# pic_k42.net
KiCad netlist of a schematic drawn in EAGLE
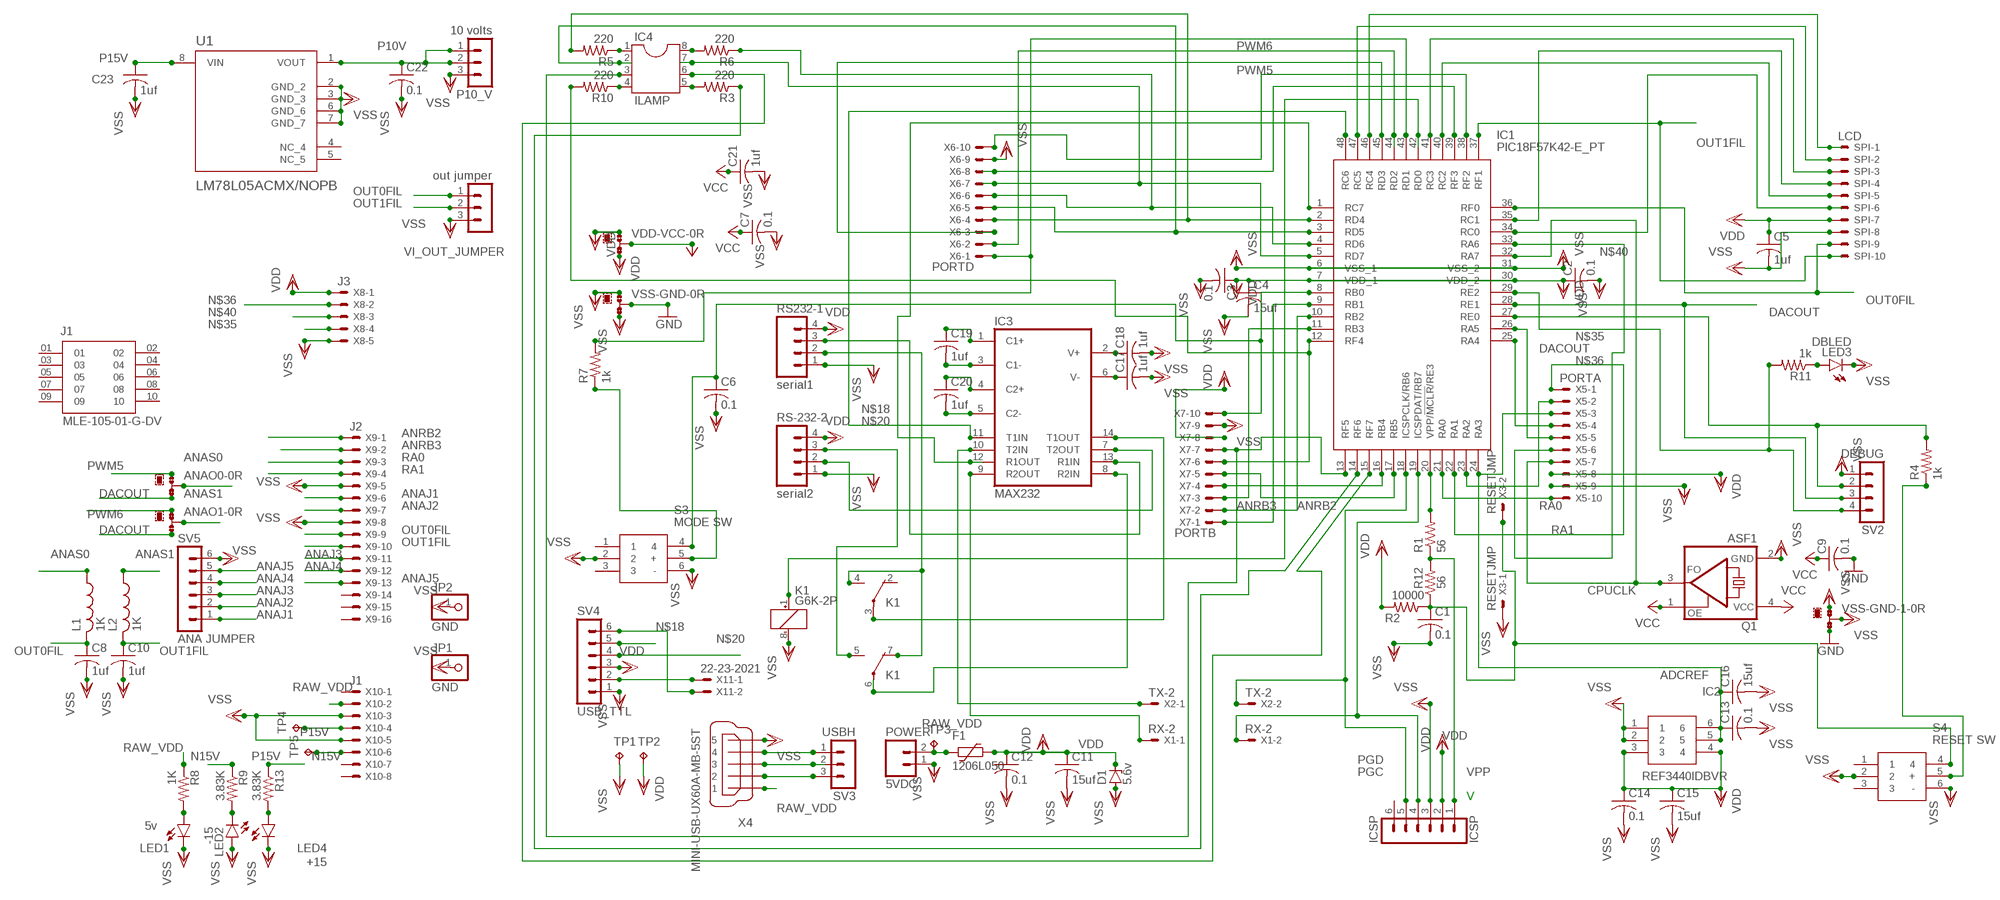
[diagram p0: schematic, sheet 1]

(export (version "E")
  (design (tool "Eeschema 10.0.6"))
  (components
    (comp (ref "ANAO0")
      (value "PS V")
      (footprint "eagle-import:A0R-JMP")
      (libsource (lib "eagle-import") (part "0R-JUMPA"))
    )
    (comp (ref "ANAO1")
      (value "PS I")
      (footprint "eagle-import:A0R-JMP")
      (libsource (lib "eagle-import") (part "0R-JUMPA"))
    )
    (comp (ref "C1")
      (value "0.1")
      (footprint "eagle-import:C1206")
      (libsource (lib "eagle-import") (part "C-USC1206"))
    )
    (comp (ref "C2")
      (value "0.1")
      (footprint "eagle-import:C1206")
      (libsource (lib "eagle-import") (part "C-USC1206"))
    )
    (comp (ref "C3")
      (value "0.1")
      (footprint "eagle-import:C1206")
      (libsource (lib "eagle-import") (part "C-USC1206"))
    )
    (comp (ref "C4")
      (value "15uf")
      (footprint "eagle-import:C1206")
      (libsource (lib "eagle-import") (part "C-USC1206"))
    )
    (comp (ref "C5")
      (value "1uf")
      (footprint "eagle-import:C0805")
      (libsource (lib "eagle-import") (part "C-USC0805"))
    )
    (comp (ref "C6")
      (value "0.1")
      (footprint "eagle-import:C1206")
      (libsource (lib "eagle-import") (part "C-USC1206"))
    )
    (comp (ref "C7")
      (value "0.1")
      (footprint "eagle-import:C1206")
      (libsource (lib "eagle-import") (part "C-USC1206"))
    )
    (comp (ref "C8")
      (value "1uf")
      (footprint "eagle-import:C0805")
      (libsource (lib "eagle-import") (part "C-USC0805"))
    )
    (comp (ref "C9")
      (value "0.1")
      (footprint "eagle-import:C1206")
      (libsource (lib "eagle-import") (part "C-USC1206"))
    )
    (comp (ref "C10")
      (value "1uf")
      (footprint "eagle-import:C0805")
      (libsource (lib "eagle-import") (part "C-USC0805"))
    )
    (comp (ref "C11")
      (value "15uf")
      (footprint "eagle-import:C1206")
      (libsource (lib "eagle-import") (part "C-USC1206"))
    )
    (comp (ref "C12")
      (value "0.1")
      (footprint "eagle-import:C1206")
      (libsource (lib "eagle-import") (part "C-USC1206"))
    )
    (comp (ref "C13")
      (value "0.1")
      (footprint "eagle-import:C1206")
      (libsource (lib "eagle-import") (part "C-USC1206"))
    )
    (comp (ref "C14")
      (value "0.1")
      (footprint "eagle-import:C1206")
      (libsource (lib "eagle-import") (part "C-USC1206"))
    )
    (comp (ref "C15")
      (value "15uf")
      (footprint "eagle-import:C1206")
      (libsource (lib "eagle-import") (part "C-USC1206"))
    )
    (comp (ref "C16")
      (value "15uf")
      (footprint "eagle-import:C1206")
      (libsource (lib "eagle-import") (part "C-USC1206"))
    )
    (comp (ref "C17")
      (value "1uf")
      (footprint "eagle-import:C0805")
      (libsource (lib "eagle-import") (part "C-USC0805"))
    )
    (comp (ref "C18")
      (value "1uf")
      (footprint "eagle-import:C0805")
      (libsource (lib "eagle-import") (part "C-USC0805"))
    )
    (comp (ref "C19")
      (value "1uf")
      (footprint "eagle-import:C0805")
      (libsource (lib "eagle-import") (part "C-USC0805"))
    )
    (comp (ref "C20")
      (value "1uf")
      (footprint "eagle-import:C0805")
      (libsource (lib "eagle-import") (part "C-USC0805"))
    )
    (comp (ref "C21")
      (value "1uf")
      (footprint "eagle-import:C0805")
      (libsource (lib "eagle-import") (part "C-USC0805"))
    )
    (comp (ref "C22")
      (value "0.1")
      (footprint "eagle-import:C1206")
      (libsource (lib "eagle-import") (part "C-USC1206"))
    )
    (comp (ref "C23")
      (value "1uf")
      (footprint "eagle-import:C0805")
      (libsource (lib "eagle-import") (part "C-USC0805"))
    )
    (comp (ref "D1")
      (value "5.6v")
      (footprint "eagle-import:DO34Z7")
      (libsource (lib "eagle-import") (part "ZENER-DIODEDO34-7"))
    )
    (comp (ref "F1")
      (value "1206L050")
      (footprint "eagle-import:1206L")
      (fields (field (name "MF") "Littelfuse"))
      (libsource (lib "eagle-import") (part "?1206L050"))
    )
    (comp (ref "IC1")
      (value "PIC18F57K42-E_PT")
      (footprint "eagle-import:QFP50P900X900X120-48N")
      (fields
        (field (name "MANUFACTURER_PART_NUMBER") "PIC18F57K42-E/PT")
        (field (name "MOUSER_PART_NUMBER") "579-PIC18F57K42-E/PT")
      )
      (libsource (lib "eagle-import") (part "PIC18F57K42-E_PT"))
    )
    (comp (ref "IC2")
      (value "REF3440IDBVR")
      (footprint "eagle-import:SOP95P280X145-6N")
      (libsource (lib "eagle-import") (part "REF3440IDBVR"))
    )
    (comp (ref "IC3")
      (value "MAX232")
      (footprint "eagle-import:DIL16")
      (fields (field (name "MF") "MAXIM") (field (name "MPN") "MAX232ACPE+"))
      (libsource (lib "eagle-import") (part "MAX232"))
    )
    (comp (ref "IC4")
      (value "ILAMP")
      (footprint "eagle-import:SOCKET-08")
      (libsource (lib "eagle-import") (part "DIL8S"))
    )
    (comp (ref "ICSP")
      (value "ICSP")
      (footprint "eagle-import:MA06-1")
      (libsource (lib "eagle-import") (part "MA06-1"))
    )
    (comp (ref "J1")
      (value "MLE-105-01-G-DV")
      (footprint "eagle-import:SAMTEC_MLE-105-01-G-DV")
      (fields (field (name "MANUFACTURER") "SAMTEC "))
      (libsource (lib "eagle-import") (part "MLE-105-01-G-DV"))
    )
    (comp (ref "JP1")
      (value "GND")
      (footprint "eagle-import:1X01")
      (libsource (lib "eagle-import") (part "PINHD-1X1"))
    )
    (comp (ref "JP2")
      (value "GND")
      (footprint "eagle-import:1X01")
      (libsource (lib "eagle-import") (part "PINHD-1X1"))
    )
    (comp (ref "K1")
      (value "G6K-2P")
      (footprint "eagle-import:G6K-2P")
      (fields (field (name "MF") "OMRON COMPONENTS USA") (field (name "MPN") "G6K-2P DC3"))
      (libsource (lib "eagle-import") (part "G6K-2P"))
    )
    (comp (ref "L1")
      (value "1K")
      (footprint "eagle-import:L2012C")
      (libsource (lib "eagle-import") (part "L-USL2012C"))
    )
    (comp (ref "L2")
      (value "1K")
      (footprint "eagle-import:L2012C")
      (libsource (lib "eagle-import") (part "L-USL2012C"))
    )
    (comp (ref "LED1")
      (value "5v")
      (footprint "eagle-import:CHIPLED_1206")
      (libsource (lib "eagle-import") (part "LEDCHIPLED_1206"))
    )
    (comp (ref "LED2")
      (value "-15")
      (footprint "eagle-import:CHIPLED_1206")
      (libsource (lib "eagle-import") (part "LEDCHIPLED_1206"))
    )
    (comp (ref "LED3")
      (value "DBLED")
      (footprint "eagle-import:CHIPLED_1206")
      (libsource (lib "eagle-import") (part "LEDCHIPLED_1206"))
    )
    (comp (ref "LED4")
      (value "+15")
      (footprint "eagle-import:CHIPLED_1206")
      (libsource (lib "eagle-import") (part "LEDCHIPLED_1206"))
    )
    (comp (ref "P10_V")
      (value "10 volts")
      (footprint "eagle-import:MA03-1")
      (libsource (lib "eagle-import") (part "MA03-1"))
    )
    (comp (ref "POWER")
      (value "5VDC")
      (footprint "eagle-import:02P")
      (libsource (lib "eagle-import") (part "M02"))
    )
    (comp (ref "Q1")
      (value "ASF1")
      (footprint "eagle-import:ASF")
      (libsource (lib "eagle-import") (part "ASF1"))
    )
    (comp (ref "R1")
      (value "56")
      (footprint "eagle-import:R1206")
      (libsource (lib "eagle-import") (part "R-US_R1206"))
    )
    (comp (ref "R2")
      (value "10000")
      (footprint "eagle-import:R1206")
      (libsource (lib "eagle-import") (part "R-US_R1206"))
    )
    (comp (ref "R3")
      (value "220")
      (footprint "eagle-import:R1206")
      (libsource (lib "eagle-import") (part "R-US_R1206"))
    )
    (comp (ref "R4")
      (value "1k")
      (footprint "eagle-import:R1206")
      (libsource (lib "eagle-import") (part "R-US_R1206"))
    )
    (comp (ref "R5")
      (value "220")
      (footprint "eagle-import:R1206")
      (libsource (lib "eagle-import") (part "R-US_R1206"))
    )
    (comp (ref "R6")
      (value "220")
      (footprint "eagle-import:R1206")
      (libsource (lib "eagle-import") (part "R-US_R1206"))
    )
    (comp (ref "R7")
      (value "1k")
      (footprint "eagle-import:R1206")
      (libsource (lib "eagle-import") (part "R-US_R1206"))
    )
    (comp (ref "R8")
      (value "1K")
      (footprint "eagle-import:R1206")
      (libsource (lib "eagle-import") (part "R-US_R1206"))
    )
    (comp (ref "R9")
      (value "3.83K")
      (footprint "eagle-import:R1206")
      (libsource (lib "eagle-import") (part "R-US_R1206"))
    )
    (comp (ref "R10")
      (value "220")
      (footprint "eagle-import:R1206")
      (libsource (lib "eagle-import") (part "R-US_R1206"))
    )
    (comp (ref "R11")
      (value "1k")
      (footprint "eagle-import:R1206")
      (libsource (lib "eagle-import") (part "R-US_R1206"))
    )
    (comp (ref "R12")
      (value "56")
      (footprint "eagle-import:R1206")
      (libsource (lib "eagle-import") (part "R-US_R1206"))
    )
    (comp (ref "R13")
      (value "3.83K")
      (footprint "eagle-import:R1206")
      (libsource (lib "eagle-import") (part "R-US_R1206"))
    )
    (comp (ref "RS-232-2")
      (value "serial2")
      (footprint "eagle-import:04P")
      (libsource (lib "eagle-import") (part "M04"))
    )
    (comp (ref "RS232-1")
      (value "serial1")
      (footprint "eagle-import:04P")
      (libsource (lib "eagle-import") (part "M04"))
    )
    (comp (ref "S3")
      (value "MODE SW")
      (footprint "eagle-import:B3W-9_1-LED")
      (fields
        (field (name "MANUFACTURER_PART_NUMBER") "B3W-9000-Y1N")
        (field (name "MOUSER_PART_NUMBER") "653-B3W-9000-Y1N")
        (field (name "RS_PART_NUMBER") "0492777P")
      )
      (libsource (lib "eagle-import") (part "B3W-9000-Y1N"))
    )
    (comp (ref "S4")
      (value "RESET SW")
      (footprint "eagle-import:B3W-9_1-LED")
      (fields
        (field (name "MANUFACTURER_PART_NUMBER") "B3W-9000-Y1N")
        (field (name "MOUSER_PART_NUMBER") "653-B3W-9000-Y1N")
        (field (name "RS_PART_NUMBER") "0492777P")
      )
      (libsource (lib "eagle-import") (part "B3W-9000-Y1N"))
    )
    (comp (ref "SPI")
      (value "LCD")
      (footprint "eagle-import:22-23-2101")
      (fields (field (name "MF") "MOLEX") (field (name "MPN") "22-23-2101"))
      (libsource (lib "eagle-import") (part "22-23-2101"))
    )
    (comp (ref "SV2")
      (value "DEBUG")
      (footprint "eagle-import:MA04-1")
      (libsource (lib "eagle-import") (part "MA04-1"))
    )
    (comp (ref "SV3")
      (value "USBH")
      (footprint "eagle-import:MA03-1")
      (libsource (lib "eagle-import") (part "MA03-1"))
    )
    (comp (ref "SV4")
      (value "USB_TTL")
      (footprint "eagle-import:MA06-1")
      (libsource (lib "eagle-import") (part "MA06-1"))
    )
    (comp (ref "SV5")
      (value "ANA JUMPER")
      (footprint "eagle-import:MA06-1")
      (libsource (lib "eagle-import") (part "MA06-1"))
    )
    (comp (ref "TP1")
      (value "TPB1,27")
      (footprint "eagle-import:B1,27")
      (libsource (lib "eagle-import") (part "TPB1,27"))
    )
    (comp (ref "TP2")
      (value "TPB1,27")
      (footprint "eagle-import:B1,27")
      (libsource (lib "eagle-import") (part "TPB1,27"))
    )
    (comp (ref "TP3")
      (value "TPB1,27")
      (footprint "eagle-import:B1,27")
      (libsource (lib "eagle-import") (part "TPB1,27"))
    )
    (comp (ref "TP4")
      (value "TPB1,27")
      (footprint "eagle-import:B1,27")
      (libsource (lib "eagle-import") (part "TPB1,27"))
    )
    (comp (ref "TP5")
      (value "TPB1,27")
      (footprint "eagle-import:B1,27")
      (libsource (lib "eagle-import") (part "TPB1,27"))
    )
    (comp (ref "U1")
      (value "LM78L05ACMX/NOPB")
      (footprint "eagle-import:SOIC127P599X175-8N")
      (fields (field (name "MF") "Texas Instruments"))
      (libsource (lib "eagle-import") (part "LM78L05ACMX/NOPB"))
    )
    (comp (ref "VDD-VCC")
      (value "VDD-VCC")
      (footprint "eagle-import:A0R-JMP")
      (libsource (lib "eagle-import") (part "0R-JUMPA"))
    )
    (comp (ref "VI_OUT_JUMPER")
      (value "out jumper")
      (footprint "eagle-import:MA03-1")
      (libsource (lib "eagle-import") (part "MA03-1"))
    )
    (comp (ref "VSS-GND")
      (value "VSS-GND")
      (footprint "eagle-import:A0R-JMP")
      (libsource (lib "eagle-import") (part "0R-JUMPA"))
    )
    (comp (ref "VSS-GND-1")
      (value "0R-JUMPA")
      (footprint "eagle-import:A0R-JMP")
      (libsource (lib "eagle-import") (part "0R-JUMPA"))
    )
    (comp (ref "X1")
      (value "RX-2")
      (footprint "eagle-import:332-02")
      (libsource (lib "eagle-import") (part "332-02"))
    )
    (comp (ref "X2")
      (value "TX-2")
      (footprint "eagle-import:332-02")
      (libsource (lib "eagle-import") (part "332-02"))
    )
    (comp (ref "X3")
      (value "RESETJMP")
      (footprint "eagle-import:332-02")
      (libsource (lib "eagle-import") (part "332-02"))
    )
    (comp (ref "X4")
      (value "MINI-USB-UX60A-MB-5ST")
      (footprint "eagle-import:UX60A-MB-5ST")
      (libsource (lib "eagle-import") (part "MINI-USB-UX60A-MB-5ST"))
    )
    (comp (ref "X5")
      (value "PORTA")
      (footprint "eagle-import:22-23-2101")
      (fields (field (name "MF") "MOLEX") (field (name "MPN") "22-23-2101"))
      (libsource (lib "eagle-import") (part "22-23-2101"))
    )
    (comp (ref "X6")
      (value "PORTD")
      (footprint "eagle-import:22-23-2101")
      (fields (field (name "MF") "MOLEX") (field (name "MPN") "22-23-2101"))
      (libsource (lib "eagle-import") (part "22-23-2101"))
    )
    (comp (ref "X7")
      (value "PORTB")
      (footprint "eagle-import:22-23-2101")
      (fields (field (name "MF") "MOLEX") (field (name "MPN") "22-23-2101"))
      (libsource (lib "eagle-import") (part "22-23-2101"))
    )
    (comp (ref "X8")
      (value "J3")
      (footprint "eagle-import:KK-156-5")
      (fields (field (name "MF") "MOLEX"))
      (libsource (lib "eagle-import") (part "KK-156-5"))
    )
    (comp (ref "X9")
      (value "J2")
      (footprint "eagle-import:KK-156-16")
      (fields (field (name "MF") "MOLEX"))
      (libsource (lib "eagle-import") (part "KK-156-16"))
    )
    (comp (ref "X10")
      (value "J1")
      (footprint "eagle-import:KK-156-8")
      (fields (field (name "MF") "MOLEX"))
      (libsource (lib "eagle-import") (part "KK-156-8"))
    )
    (comp (ref "X11")
      (value "22-23-2021")
      (footprint "eagle-import:22-23-2021")
      (fields (field (name "MF") "MOLEX"))
      (libsource (lib "eagle-import") (part "22-23-2021"))
    )
  )
  (nets
    (net (code "1") (name "/ADCREF") (class "Default")
      (node (ref "C13") (pin "1") (pinfunction "1_1") (pintype "passive"))
      (node (ref "C16") (pin "1") (pinfunction "1_1") (pintype "passive"))
      (node (ref "IC1") (pin "24") (pinfunction "RA3_24") (pintype "bidirectional"))
      (node (ref "IC2") (pin "5") (pinfunction "5_5") (pintype "bidirectional"))
      (node (ref "IC2") (pin "6") (pinfunction "6_6") (pintype "bidirectional"))
      (node (ref "X5") (pin "3") (pinfunction "S_3") (pintype "passive"))
    )
    (net (code "2") (name "/ANAJ1") (class "Default")
      (node (ref "SV5") (pin "1") (pinfunction "1_1") (pintype "passive"))
      (node (ref "X9") (pin "6") (pinfunction "S_6") (pintype "passive"))
    )
    (net (code "3") (name "/ANAJ2") (class "Default")
      (node (ref "SV5") (pin "2") (pinfunction "2_2") (pintype "passive"))
      (node (ref "X9") (pin "7") (pinfunction "S_7") (pintype "passive"))
    )
    (net (code "4") (name "/ANAJ3") (class "Default")
      (node (ref "SV5") (pin "3") (pinfunction "3_3") (pintype "passive"))
      (node (ref "X9") (pin "11") (pinfunction "S_11") (pintype "passive"))
    )
    (net (code "5") (name "/ANAJ4") (class "Default")
      (node (ref "SV5") (pin "4") (pinfunction "4_4") (pintype "passive"))
      (node (ref "X9") (pin "12") (pinfunction "S_12") (pintype "passive"))
    )
    (net (code "6") (name "/ANAJ5") (class "Default")
      (node (ref "SV5") (pin "5") (pinfunction "5_5") (pintype "passive"))
      (node (ref "X9") (pin "13") (pinfunction "S_13") (pintype "passive"))
    )
    (net (code "7") (name "/ANAS0") (class "Default")
      (node (ref "ANAO0") (pin "2") (pinfunction "2_2") (pintype "passive"))
      (node (ref "L1") (pin "1") (pinfunction "1_1") (pintype "passive"))
    )
    (net (code "8") (name "/ANAS1") (class "Default")
      (node (ref "ANAO1") (pin "2") (pinfunction "2_2") (pintype "passive"))
      (node (ref "L2") (pin "1") (pinfunction "1_1") (pintype "passive"))
    )
    (net (code "9") (name "/ANRB2") (class "Default")
      (node (ref "IC1") (pin "10") (pinfunction "RB2_10") (pintype "bidirectional"))
      (node (ref "X7") (pin "2") (pinfunction "S_2") (pintype "passive"))
      (node (ref "X9") (pin "1") (pinfunction "S_1") (pintype "passive"))
    )
    (net (code "10") (name "/ANRB3") (class "Default")
      (node (ref "IC1") (pin "11") (pinfunction "RB3_11") (pintype "bidirectional"))
      (node (ref "X7") (pin "3") (pinfunction "S_3") (pintype "passive"))
      (node (ref "X9") (pin "2") (pinfunction "S_2") (pintype "passive"))
    )
    (net (code "11") (name "/CPUCLK") (class "Default")
      (node (ref "IC1") (pin "32") (pinfunction "RA7_32") (pintype "bidirectional"))
      (node (ref "Q1") (pin "3") (pinfunction "FO_3") (pintype "output"))
      (node (ref "X5") (pin "7") (pinfunction "S_7") (pintype "passive"))
    )
    (net (code "12") (name "/DACOUT") (class "Default")
      (node (ref "ANAO0") (pin "3") (pinfunction "3_3") (pintype "passive"))
      (node (ref "ANAO1") (pin "3") (pinfunction "3_3") (pintype "passive"))
      (node (ref "IC1") (pin "23") (pinfunction "RA2_23") (pintype "bidirectional"))
      (node (ref "IC1") (pin "28") (pinfunction "RE1_28") (pintype "bidirectional"))
      (node (ref "SV2") (pin "3") (pinfunction "3_3") (pintype "passive"))
      (node (ref "X5") (pin "2") (pinfunction "S_2") (pintype "passive"))
    )
    (net (code "13") (name "/N$18") (class "Default")
      (node (ref "IC1") (pin "1") (pinfunction "RC7_1") (pintype "bidirectional"))
      (node (ref "IC3") (pin "12") (pinfunction "R1OUT_12") (pintype "output"))
      (node (ref "SV4") (pin "5") (pinfunction "5_5") (pintype "passive"))
    )
    (net (code "14") (name "/N$20") (class "Default")
      (node (ref "IC1") (pin "48") (pinfunction "RC6_48") (pintype "bidirectional"))
      (node (ref "IC3") (pin "11") (pinfunction "T1IN_11") (pintype "input"))
      (node (ref "SV4") (pin "4") (pinfunction "4_4") (pintype "passive"))
    )
    (net (code "15") (name "/N$35") (class "Default")
      (node (ref "IC1") (pin "26") (pinfunction "RA5_26") (pintype "bidirectional"))
      (node (ref "X5") (pin "5") (pinfunction "S_5") (pintype "passive"))
      (node (ref "X8") (pin "4") (pinfunction "S_4") (pintype "passive"))
    )
    (net (code "16") (name "/N$36") (class "Default")
      (node (ref "IC1") (pin "25") (pinfunction "RA4_25") (pintype "bidirectional"))
      (node (ref "X5") (pin "4") (pinfunction "S_4") (pintype "passive"))
      (node (ref "X8") (pin "2") (pinfunction "S_2") (pintype "passive"))
    )
    (net (code "17") (name "/N$40") (class "Default")
      (node (ref "IC1") (pin "33") (pinfunction "RA6_33") (pintype "bidirectional"))
      (node (ref "X5") (pin "6") (pinfunction "S_6") (pintype "passive"))
      (node (ref "X8") (pin "3") (pinfunction "S_3") (pintype "passive"))
    )
    (net (code "18") (name "/N15V") (class "Default")
      (node (ref "R9") (pin "1") (pinfunction "1_1") (pintype "passive"))
      (node (ref "TP5") (pin "TP") (pinfunction "TP_TP") (pintype "input"))
      (node (ref "X10") (pin "6") (pinfunction "S_6") (pintype "passive"))
    )
    (net (code "19") (name "/NC_4") (class "Default")
      (node (ref "U1") (pin "4") (pinfunction "NC_4_4") (pintype "power_in"))
    )
    (net (code "20") (name "/NC_5") (class "Default")
      (node (ref "U1") (pin "5") (pinfunction "NC_5_5") (pintype "power_in"))
    )
    (net (code "21") (name "/OUT0FIL") (class "Default")
      (node (ref "C8") (pin "1") (pinfunction "1_1") (pintype "passive"))
      (node (ref "IC1") (pin "36") (pinfunction "RF0_36") (pintype "bidirectional"))
      (node (ref "L1") (pin "2") (pinfunction "2_2") (pintype "passive"))
      (node (ref "SPI") (pin "9") (pinfunction "S_9") (pintype "passive"))
      (node (ref "VI_OUT_JUMPER") (pin "1") (pinfunction "1_1") (pintype "passive"))
      (node (ref "X9") (pin "9") (pinfunction "S_9") (pintype "passive"))
    )
    (net (code "22") (name "/OUT1FIL") (class "Default")
      (node (ref "C10") (pin "1") (pinfunction "1_1") (pintype "passive"))
      (node (ref "IC1") (pin "37") (pinfunction "RF1_37") (pintype "bidirectional"))
      (node (ref "L2") (pin "2") (pinfunction "2_2") (pintype "passive"))
      (node (ref "SPI") (pin "10") (pinfunction "S_10") (pintype "passive"))
      (node (ref "VI_OUT_JUMPER") (pin "2") (pinfunction "2_2") (pintype "passive"))
      (node (ref "X9") (pin "10") (pinfunction "S_10") (pintype "passive"))
    )
    (net (code "23") (name "/P10V") (class "Default")
      (node (ref "C22") (pin "1") (pinfunction "1_1") (pintype "passive"))
      (node (ref "P10_V") (pin "1") (pinfunction "1_1") (pintype "passive"))
      (node (ref "P10_V") (pin "2") (pinfunction "2_2") (pintype "passive"))
      (node (ref "U1") (pin "1") (pinfunction "VOUT_1") (pintype "output"))
    )
    (net (code "24") (name "/P15V") (class "Default")
      (node (ref "C23") (pin "1") (pinfunction "1_1") (pintype "passive"))
      (node (ref "R13") (pin "1") (pinfunction "1_1") (pintype "passive"))
      (node (ref "TP4") (pin "TP") (pinfunction "TP_TP") (pintype "input"))
      (node (ref "U1") (pin "8") (pinfunction "VIN_8") (pintype "input"))
      (node (ref "X10") (pin "4") (pinfunction "S_4") (pintype "passive"))
    )
    (net (code "25") (name "/PGC") (class "Default")
      (node (ref "IC1") (pin "18") (pinfunction "ICSPCLK/RB6_18") (pintype "bidirectional"))
      (node (ref "ICSP") (pin "5") (pinfunction "5_5") (pintype "passive"))
      (node (ref "X2") (pin "2") (pinfunction "S_2") (pintype "passive"))
    )
    (net (code "26") (name "/PGD") (class "Default")
      (node (ref "IC1") (pin "19") (pinfunction "ICSPDAT/RB7_19") (pintype "bidirectional"))
      (node (ref "ICSP") (pin "4") (pinfunction "4_4") (pintype "passive"))
      (node (ref "X1") (pin "2") (pinfunction "S_2") (pintype "passive"))
    )
    (net (code "27") (name "/PWM5") (class "Default")
      (node (ref "ANAO0") (pin "1") (pinfunction "1_1") (pintype "passive"))
      (node (ref "IC1") (pin "38") (pinfunction "RF2_38") (pintype "bidirectional"))
      (node (ref "X6") (pin "10") (pinfunction "S_10") (pintype "passive"))
    )
    (net (code "28") (name "/PWM6") (class "Default")
      (node (ref "ANAO1") (pin "1") (pinfunction "1_1") (pintype "passive"))
      (node (ref "IC1") (pin "44") (pinfunction "RD2_44") (pintype "bidirectional"))
      (node (ref "X6") (pin "2") (pinfunction "S_2") (pintype "passive"))
    )
    (net (code "29") (name "/RA0") (class "Default")
      (node (ref "IC1") (pin "21") (pinfunction "RA0_21") (pintype "bidirectional"))
      (node (ref "X5") (pin "10") (pinfunction "S_10") (pintype "passive"))
      (node (ref "X9") (pin "3") (pinfunction "S_3") (pintype "passive"))
    )
    (net (code "30") (name "/RA1") (class "Default")
      (node (ref "IC1") (pin "22") (pinfunction "RA1_22") (pintype "bidirectional"))
      (node (ref "X5") (pin "1") (pinfunction "S_1") (pintype "passive"))
      (node (ref "X9") (pin "4") (pinfunction "S_4") (pintype "passive"))
    )
    (net (code "31") (name "/RAW_VDD") (class "Default")
      (node (ref "F1") (pin "2") (pinfunction "2_2") (pintype "passive"))
      (node (ref "POWER") (pin "2") (pinfunction "2_2") (pintype "passive"))
      (node (ref "R8") (pin "1") (pinfunction "1_1") (pintype "passive"))
      (node (ref "TP3") (pin "TP") (pinfunction "TP_TP") (pintype "input"))
      (node (ref "X10") (pin "2") (pinfunction "S_2") (pintype "passive"))
      (node (ref "X4") (pin "1") (pinfunction "1_1") (pintype "input"))
    )
    (net (code "32") (name "/VPP") (class "Default")
      (node (ref "ICSP") (pin "1") (pinfunction "1_1") (pintype "passive"))
      (node (ref "R1") (pin "1") (pinfunction "1_1") (pintype "passive"))
      (node (ref "R12") (pin "2") (pinfunction "2_2") (pintype "passive"))
    )
    (net (code "33") (name "GND") (class "Default")
      (node (ref "C9") (pin "2") (pinfunction "2_2") (pintype "passive"))
      (node (ref "VSS-GND") (pin "2") (pinfunction "2_2") (pintype "passive"))
      (node (ref "VSS-GND-1") (pin "3") (pinfunction "3_3") (pintype "passive"))
    )
    (net (code "34") (name "Net-(IC1-RB0)") (class "Default")
      (node (ref "C6") (pin "1") (pinfunction "1_1") (pintype "passive"))
      (node (ref "IC1") (pin "8") (pinfunction "RB0_8") (pintype "bidirectional"))
      (node (ref "S3") (pin "4") (pinfunction "4_4") (pintype "bidirectional"))
      (node (ref "X7") (pin "10") (pinfunction "S_10") (pintype "passive"))
    )
    (net (code "35") (name "Net-(IC1-RB1)") (class "Default")
      (node (ref "IC1") (pin "9") (pinfunction "RB1_9") (pintype "bidirectional"))
      (node (ref "X7") (pin "1") (pinfunction "S_1") (pintype "passive"))
    )
    (net (code "36") (name "Net-(IC1-RB4)") (class "Default")
      (node (ref "IC1") (pin "16") (pinfunction "RB4_16") (pintype "bidirectional"))
      (node (ref "X7") (pin "4") (pinfunction "S_4") (pintype "passive"))
    )
    (net (code "37") (name "Net-(IC1-RB5)") (class "Default")
      (node (ref "IC1") (pin "17") (pinfunction "RB5_17") (pintype "bidirectional"))
      (node (ref "X7") (pin "5") (pinfunction "S_5") (pintype "passive"))
    )
    (net (code "38") (name "Net-(IC1-RC0)") (class "Default")
      (node (ref "IC1") (pin "34") (pinfunction "RC0_34") (pintype "bidirectional"))
      (node (ref "SPI") (pin "6") (pinfunction "S_6") (pintype "passive"))
    )
    (net (code "39") (name "Net-(IC1-RC1)") (class "Default")
      (node (ref "IC1") (pin "35") (pinfunction "RC1_35") (pintype "bidirectional"))
      (node (ref "SPI") (pin "4") (pinfunction "S_4") (pintype "passive"))
    )
    (net (code "40") (name "Net-(IC1-RC2)") (class "Default")
      (node (ref "IC1") (pin "40") (pinfunction "RC2_40") (pintype "bidirectional"))
      (node (ref "SPI") (pin "5") (pinfunction "S_5") (pintype "passive"))
    )
    (net (code "41") (name "Net-(IC1-RC3)") (class "Default")
      (node (ref "IC1") (pin "41") (pinfunction "RC3_41") (pintype "bidirectional"))
      (node (ref "SPI") (pin "3") (pinfunction "S_3") (pintype "passive"))
    )
    (net (code "42") (name "Net-(IC1-RC4)") (class "Default")
      (node (ref "IC1") (pin "46") (pinfunction "RC4_46") (pintype "bidirectional"))
      (node (ref "SPI") (pin "1") (pinfunction "S_1") (pintype "passive"))
    )
    (net (code "43") (name "Net-(IC1-RC5)") (class "Default")
      (node (ref "IC1") (pin "47") (pinfunction "RC5_47") (pintype "bidirectional"))
      (node (ref "SPI") (pin "2") (pinfunction "S_2") (pintype "passive"))
    )
    (net (code "44") (name "Net-(IC1-RD0)") (class "Default")
      (node (ref "IC1") (pin "42") (pinfunction "RD0_42") (pintype "bidirectional"))
      (node (ref "K1") (pin "1") (pinfunction "+_1") (pintype "passive"))
    )
    (net (code "45") (name "Net-(IC1-RD1)") (class "Default")
      (node (ref "IC1") (pin "43") (pinfunction "RD1_43") (pintype "bidirectional"))
      (node (ref "R7") (pin "2") (pinfunction "2_2") (pintype "passive"))
      (node (ref "X6") (pin "1") (pinfunction "S_1") (pintype "passive"))
    )
    (net (code "46") (name "Net-(IC1-RD3)") (class "Default")
      (node (ref "IC1") (pin "45") (pinfunction "RD3_45") (pintype "bidirectional"))
      (node (ref "X6") (pin "3") (pinfunction "S_3") (pintype "passive"))
    )
    (net (code "47") (name "Net-(IC1-RD4)") (class "Default")
      (node (ref "IC1") (pin "2") (pinfunction "RD4_2") (pintype "bidirectional"))
      (node (ref "R5") (pin "2") (pinfunction "2_2") (pintype "passive"))
      (node (ref "X6") (pin "4") (pinfunction "S_4") (pintype "passive"))
    )
    (net (code "48") (name "Net-(IC1-RD5)") (class "Default")
      (node (ref "IC1") (pin "3") (pinfunction "RD5_3") (pintype "bidirectional"))
      (node (ref "IC4") (pin "2") (pinfunction "2_2") (pintype "passive"))
      (node (ref "X6") (pin "5") (pinfunction "S_5") (pintype "passive"))
    )
    (net (code "49") (name "Net-(IC1-RD6)") (class "Default")
      (node (ref "IC1") (pin "4") (pinfunction "RD6_4") (pintype "bidirectional"))
      (node (ref "R6") (pin "1") (pinfunction "1_1") (pintype "passive"))
      (node (ref "X6") (pin "6") (pinfunction "S_6") (pintype "passive"))
    )
    (net (code "50") (name "Net-(IC1-RD7)") (class "Default")
      (node (ref "IC1") (pin "5") (pinfunction "RD7_5") (pintype "bidirectional"))
      (node (ref "IC4") (pin "7") (pinfunction "7_7") (pintype "passive"))
      (node (ref "X6") (pin "7") (pinfunction "S_7") (pintype "passive"))
    )
    (net (code "51") (name "Net-(IC1-RE0)") (class "Default")
      (node (ref "IC1") (pin "27") (pinfunction "RE0_27") (pintype "bidirectional"))
      (node (ref "R4") (pin "2") (pinfunction "2_2") (pintype "passive"))
      (node (ref "SV2") (pin "2") (pinfunction "2_2") (pintype "passive"))
    )
    (net (code "52") (name "Net-(IC1-RE2)") (class "Default")
      (node (ref "IC1") (pin "29") (pinfunction "RE2_29") (pintype "bidirectional"))
      (node (ref "R11") (pin "2") (pinfunction "2_2") (pintype "passive"))
      (node (ref "SV2") (pin "4") (pinfunction "4_4") (pintype "passive"))
    )
    (net (code "53") (name "Net-(IC1-RF3)") (class "Default")
      (node (ref "IC1") (pin "39") (pinfunction "RF3_39") (pintype "bidirectional"))
      (node (ref "X6") (pin "8") (pinfunction "S_8") (pintype "passive"))
    )
    (net (code "54") (name "Net-(IC1-RF4)") (class "Default")
      (node (ref "IC1") (pin "12") (pinfunction "RF4_12") (pintype "bidirectional"))
      (node (ref "R10") (pin "2") (pinfunction "2_2") (pintype "passive"))
      (node (ref "X7") (pin "6") (pinfunction "S_6") (pintype "passive"))
    )
    (net (code "55") (name "Net-(IC1-RF5)") (class "Default")
      (node (ref "IC1") (pin "13") (pinfunction "RF5_13") (pintype "bidirectional"))
      (node (ref "IC4") (pin "3") (pinfunction "3_3") (pintype "passive"))
      (node (ref "X7") (pin "7") (pinfunction "S_7") (pintype "passive"))
    )
    (net (code "56") (name "Net-(IC1-RF6)") (class "Default")
      (node (ref "IC1") (pin "14") (pinfunction "RF6_14") (pintype "bidirectional"))
      (node (ref "R3") (pin "1") (pinfunction "1_1") (pintype "passive"))
    )
    (net (code "57") (name "Net-(IC1-RF7)") (class "Default")
      (node (ref "IC1") (pin "15") (pinfunction "RF7_15") (pintype "bidirectional"))
      (node (ref "IC4") (pin "6") (pinfunction "6_6") (pintype "passive"))
    )
    (net (code "58") (name "Net-(IC1-VPP{slash}~{MCLR}{slash}RE3)") (class "Default")
      (node (ref "IC1") (pin "20") (pinfunction "VPP/~{MCLR}/RE3_20") (pintype "bidirectional"))
      (node (ref "R1") (pin "2") (pinfunction "2_2") (pintype "passive"))
    )
    (net (code "59") (name "Net-(IC3A-C1+)") (class "Default")
      (node (ref "C19") (pin "1") (pinfunction "1_1") (pintype "passive"))
      (node (ref "IC3") (pin "1") (pinfunction "C1+_1") (pintype "bidirectional"))
    )
    (net (code "60") (name "Net-(IC3A-C1-)") (class "Default")
      (node (ref "C19") (pin "2") (pinfunction "2_2") (pintype "passive"))
      (node (ref "IC3") (pin "3") (pinfunction "C1-_3") (pintype "bidirectional"))
    )
    (net (code "61") (name "Net-(IC3A-C2+)") (class "Default")
      (node (ref "C20") (pin "1") (pinfunction "1_1") (pintype "passive"))
      (node (ref "IC3") (pin "4") (pinfunction "C2+_4") (pintype "bidirectional"))
    )
    (net (code "62") (name "Net-(IC3A-C2-)") (class "Default")
      (node (ref "C20") (pin "2") (pinfunction "2_2") (pintype "passive"))
      (node (ref "IC3") (pin "5") (pinfunction "C2-_5") (pintype "bidirectional"))
    )
    (net (code "63") (name "Net-(IC3A-R1IN)") (class "Default")
      (node (ref "IC3") (pin "13") (pinfunction "R1IN_13") (pintype "input"))
      (node (ref "RS232-1") (pin "3") (pinfunction "3_3") (pintype "passive"))
    )
    (net (code "64") (name "Net-(IC3A-R2IN)") (class "Default")
      (node (ref "IC3") (pin "8") (pinfunction "R2IN_8") (pintype "input"))
      (node (ref "K1") (pin "6") (pinfunction "P_6") (pintype "passive"))
    )
    (net (code "65") (name "Net-(IC3A-R2OUT)") (class "Default")
      (node (ref "IC3") (pin "9") (pinfunction "R2OUT_9") (pintype "output"))
      (node (ref "X1") (pin "1") (pinfunction "S_1") (pintype "passive"))
    )
    (net (code "66") (name "Net-(IC3A-T1OUT)") (class "Default")
      (node (ref "IC3") (pin "14") (pinfunction "T1OUT_14") (pintype "output"))
      (node (ref "K1") (pin "3") (pinfunction "P_3") (pintype "passive"))
    )
    (net (code "67") (name "Net-(IC3A-T2IN)") (class "Default")
      (node (ref "IC3") (pin "10") (pinfunction "T2IN_10") (pintype "input"))
      (node (ref "X2") (pin "1") (pinfunction "S_1") (pintype "passive"))
    )
    (net (code "68") (name "Net-(IC3A-T2OUT)") (class "Default")
      (node (ref "IC3") (pin "7") (pinfunction "T2OUT_7") (pintype "output"))
      (node (ref "RS-232-2") (pin "2") (pinfunction "2_2") (pintype "passive"))
    )
    (net (code "69") (name "Net-(IC3A-V+)") (class "Default")
      (node (ref "C18") (pin "1") (pinfunction "1_1") (pintype "passive"))
      (node (ref "IC3") (pin "2") (pinfunction "V+_2") (pintype "bidirectional"))
    )
    (net (code "70") (name "Net-(IC3A-V-)") (class "Default")
      (node (ref "C17") (pin "1") (pinfunction "1_1") (pintype "passive"))
      (node (ref "IC3") (pin "6") (pinfunction "V-_6") (pintype "bidirectional"))
    )
    (net (code "71") (name "Net-(IC4-Pad1)") (class "Default")
      (node (ref "IC4") (pin "1") (pinfunction "1_1") (pintype "passive"))
      (node (ref "R5") (pin "1") (pinfunction "1_1") (pintype "passive"))
    )
    (net (code "72") (name "Net-(IC4-Pad4)") (class "Default")
      (node (ref "IC4") (pin "4") (pinfunction "4_4") (pintype "passive"))
      (node (ref "R10") (pin "1") (pinfunction "1_1") (pintype "passive"))
    )
    (net (code "73") (name "Net-(IC4-Pad5)") (class "Default")
      (node (ref "IC4") (pin "5") (pinfunction "5_5") (pintype "passive"))
      (node (ref "R3") (pin "2") (pinfunction "2_2") (pintype "passive"))
    )
    (net (code "74") (name "Net-(IC4-Pad8)") (class "Default")
      (node (ref "IC4") (pin "8") (pinfunction "8_8") (pintype "passive"))
      (node (ref "R6") (pin "2") (pinfunction "2_2") (pintype "passive"))
    )
    (net (code "75") (name "Net-(K1B-S)") (class "Default")
      (node (ref "K1") (pin "4") (pinfunction "S_4") (pintype "passive"))
      (node (ref "K1") (pin "7") (pinfunction "O_7") (pintype "passive"))
      (node (ref "RS232-1") (pin "2") (pinfunction "2_2") (pintype "passive"))
    )
    (net (code "76") (name "Net-(K1C-S)") (class "Default")
      (node (ref "K1") (pin "5") (pinfunction "S_5") (pintype "passive"))
      (node (ref "RS-232-2") (pin "3") (pinfunction "3_3") (pintype "passive"))
    )
    (net (code "77") (name "Net-(LED1-PadA)") (class "Default")
      (node (ref "LED1") (pin "A") (pinfunction "A_A") (pintype "passive"))
      (node (ref "R8") (pin "2") (pinfunction "2_2") (pintype "passive"))
    )
    (net (code "78") (name "Net-(LED2-PadC)") (class "Default")
      (node (ref "LED2") (pin "C") (pinfunction "C_C") (pintype "passive"))
      (node (ref "R9") (pin "2") (pinfunction "2_2") (pintype "passive"))
    )
    (net (code "79") (name "Net-(LED3-PadA)") (class "Default")
      (node (ref "LED3") (pin "A") (pinfunction "A_A") (pintype "passive"))
      (node (ref "R11") (pin "1") (pinfunction "1_1") (pintype "passive"))
    )
    (net (code "80") (name "Net-(LED4-PadA)") (class "Default")
      (node (ref "LED4") (pin "A") (pinfunction "A_A") (pintype "passive"))
      (node (ref "R13") (pin "2") (pinfunction "2_2") (pintype "passive"))
    )
    (net (code "81") (name "Net-(S3-+)") (class "Default")
      (node (ref "R7") (pin "1") (pinfunction "1_1") (pintype "passive"))
      (node (ref "S3") (pin "5") (pinfunction "+_5") (pintype "bidirectional"))
    )
    (net (code "82") (name "Net-(S4-+)") (class "Default")
      (node (ref "R4") (pin "1") (pinfunction "1_1") (pintype "passive"))
      (node (ref "S4") (pin "5") (pinfunction "+_5") (pintype "bidirectional"))
    )
    (net (code "83") (name "Net-(SV3-Pad1)") (class "Default")
      (node (ref "SV3") (pin "1") (pinfunction "1_1") (pintype "passive"))
      (node (ref "X4") (pin "4") (pinfunction "4_4") (pintype "input"))
    )
    (net (code "84") (name "Net-(SV3-Pad2)") (class "Default")
      (node (ref "SV3") (pin "2") (pinfunction "2_2") (pintype "passive"))
      (node (ref "X4") (pin "3") (pinfunction "3_3") (pintype "input"))
    )
    (net (code "85") (name "Net-(SV3-Pad3)") (class "Default")
      (node (ref "SV3") (pin "3") (pinfunction "3_3") (pintype "passive"))
      (node (ref "X4") (pin "2") (pinfunction "2_2") (pintype "input"))
    )
    (net (code "86") (name "Net-(X3B-S)") (class "Default")
      (node (ref "C1") (pin "1") (pinfunction "1_1") (pintype "passive"))
      (node (ref "R12") (pin "1") (pinfunction "1_1") (pintype "passive"))
      (node (ref "R2") (pin "1") (pinfunction "1_1") (pintype "passive"))
      (node (ref "S4") (pin "4") (pinfunction "4_4") (pintype "bidirectional"))
      (node (ref "X3") (pin "2") (pinfunction "S_2") (pintype "passive"))
    )
    (net (code "87") (name "Net-(X11A-S)") (class "Default")
      (node (ref "SV4") (pin "2") (pinfunction "2_2") (pintype "passive"))
      (node (ref "X11") (pin "1") (pinfunction "S_1") (pintype "passive"))
    )
    (net (code "88") (name "Net-(X11B-S)") (class "Default")
      (node (ref "SV4") (pin "6") (pinfunction "6_6") (pintype "passive"))
      (node (ref "X11") (pin "2") (pinfunction "S_2") (pintype "passive"))
    )
    (net (code "89") (name "VCC") (class "Default")
      (node (ref "C21") (pin "1") (pinfunction "1_1") (pintype "passive"))
      (node (ref "C7") (pin "1") (pinfunction "1_1") (pintype "passive"))
      (node (ref "C9") (pin "1") (pinfunction "1_1") (pintype "passive"))
      (node (ref "Q1") (pin "1") (pinfunction "OE_1") (pintype "input"))
      (node (ref "Q1") (pin "4") (pinfunction "VCC_4") (pintype "power_in"))
      (node (ref "VDD-VCC") (pin "2") (pinfunction "2_2") (pintype "passive"))
    )
    (net (code "90") (name "VDD") (class "Default")
      (node (ref "C11") (pin "1") (pinfunction "1_1") (pintype "passive"))
      (node (ref "C12") (pin "1") (pinfunction "1_1") (pintype "passive"))
      (node (ref "C14") (pin "1") (pinfunction "1_1") (pintype "passive"))
      (node (ref "C15") (pin "1") (pinfunction "1_1") (pintype "passive"))
      (node (ref "C2") (pin "1") (pinfunction "1_1") (pintype "passive"))
      (node (ref "C3") (pin "1") (pinfunction "1_1") (pintype "passive"))
      (node (ref "C4") (pin "1") (pinfunction "1_1") (pintype "passive"))
      (node (ref "C5") (pin "1") (pinfunction "1_1") (pintype "passive"))
      (node (ref "D1") (pin "C") (pinfunction "C_C") (pintype "passive"))
      (node (ref "F1") (pin "1") (pinfunction "1_1") (pintype "passive"))
      (node (ref "IC1") (pin "30") (pinfunction "VDD_2_30") (pintype "bidirectional"))
      (node (ref "IC1") (pin "7") (pinfunction "VDD_1_7") (pintype "bidirectional"))
      (node (ref "IC2") (pin "3") (pinfunction "3_3") (pintype "bidirectional"))
      (node (ref "IC2") (pin "4") (pinfunction "4_4") (pintype "bidirectional"))
      (node (ref "ICSP") (pin "2") (pinfunction "2_2") (pintype "passive"))
      (node (ref "R2") (pin "2") (pinfunction "2_2") (pintype "passive"))
      (node (ref "RS-232-2") (pin "4") (pinfunction "4_4") (pintype "passive"))
      (node (ref "RS232-1") (pin "4") (pinfunction "4_4") (pintype "passive"))
      (node (ref "SPI") (pin "7") (pinfunction "S_7") (pintype "passive"))
      (node (ref "SV4") (pin "3") (pinfunction "3_3") (pintype "passive"))
      (node (ref "TP2") (pin "TP") (pinfunction "TP_TP") (pintype "input"))
      (node (ref "VDD-VCC") (pin "1") (pinfunction "1_1") (pintype "passive"))
      (node (ref "VDD-VCC") (pin "3") (pinfunction "3_3") (pintype "passive"))
      (node (ref "X5") (pin "8") (pinfunction "S_8") (pintype "passive"))
      (node (ref "X7") (pin "8") (pinfunction "S_8") (pintype "passive"))
      (node (ref "X8") (pin "1") (pinfunction "S_1") (pintype "passive"))
    )
    (net (code "91") (name "VSS") (class "Default")
      (node (ref "C1") (pin "2") (pinfunction "2_2") (pintype "passive"))
      (node (ref "C10") (pin "2") (pinfunction "2_2") (pintype "passive"))
      (node (ref "C11") (pin "2") (pinfunction "2_2") (pintype "passive"))
      (node (ref "C12") (pin "2") (pinfunction "2_2") (pintype "passive"))
      (node (ref "C13") (pin "2") (pinfunction "2_2") (pintype "passive"))
      (node (ref "C14") (pin "2") (pinfunction "2_2") (pintype "passive"))
      (node (ref "C15") (pin "2") (pinfunction "2_2") (pintype "passive"))
      (node (ref "C16") (pin "2") (pinfunction "2_2") (pintype "passive"))
      (node (ref "C17") (pin "2") (pinfunction "2_2") (pintype "passive"))
      (node (ref "C18") (pin "2") (pinfunction "2_2") (pintype "passive"))
      (node (ref "C2") (pin "2") (pinfunction "2_2") (pintype "passive"))
      (node (ref "C21") (pin "2") (pinfunction "2_2") (pintype "passive"))
      (node (ref "C22") (pin "2") (pinfunction "2_2") (pintype "passive"))
      (node (ref "C23") (pin "2") (pinfunction "2_2") (pintype "passive"))
      (node (ref "C3") (pin "2") (pinfunction "2_2") (pintype "passive"))
      (node (ref "C4") (pin "2") (pinfunction "2_2") (pintype "passive"))
      (node (ref "C5") (pin "2") (pinfunction "2_2") (pintype "passive"))
      (node (ref "C6") (pin "2") (pinfunction "2_2") (pintype "passive"))
      (node (ref "C7") (pin "2") (pinfunction "2_2") (pintype "passive"))
      (node (ref "C8") (pin "2") (pinfunction "2_2") (pintype "passive"))
      (node (ref "D1") (pin "A") (pinfunction "A_A") (pintype "passive"))
      (node (ref "IC1") (pin "31") (pinfunction "VSS_2_31") (pintype "bidirectional"))
      (node (ref "IC1") (pin "6") (pinfunction "VSS_1_6") (pintype "bidirectional"))
      (node (ref "IC2") (pin "1") (pinfunction "1_1") (pintype "bidirectional"))
      (node (ref "IC2") (pin "2") (pinfunction "2_2") (pintype "bidirectional"))
      (node (ref "ICSP") (pin "3") (pinfunction "3_3") (pintype "passive"))
      (node (ref "JP1") (pin "1") (pinfunction "1_1") (pintype "passive"))
      (node (ref "JP2") (pin "1") (pinfunction "1_1") (pintype "passive"))
      (node (ref "K1") (pin "8") (pinfunction "-_8") (pintype "passive"))
      (node (ref "LED1") (pin "C") (pinfunction "C_C") (pintype "passive"))
      (node (ref "LED2") (pin "A") (pinfunction "A_A") (pintype "passive"))
      (node (ref "LED3") (pin "C") (pinfunction "C_C") (pintype "passive"))
      (node (ref "LED4") (pin "C") (pinfunction "C_C") (pintype "passive"))
      (node (ref "P10_V") (pin "3") (pinfunction "3_3") (pintype "passive"))
      (node (ref "POWER") (pin "1") (pinfunction "1_1") (pintype "passive"))
      (node (ref "Q1") (pin "2") (pinfunction "GND_2") (pintype "power_in"))
      (node (ref "RS-232-2") (pin "1") (pinfunction "1_1") (pintype "passive"))
      (node (ref "RS232-1") (pin "1") (pinfunction "1_1") (pintype "passive"))
      (node (ref "S3") (pin "2") (pinfunction "2_2") (pintype "bidirectional"))
      (node (ref "S3") (pin "6") (pinfunction "-_6") (pintype "bidirectional"))
      (node (ref "S4") (pin "2") (pinfunction "2_2") (pintype "bidirectional"))
      (node (ref "S4") (pin "6") (pinfunction "-_6") (pintype "bidirectional"))
      (node (ref "SPI") (pin "8") (pinfunction "S_8") (pintype "passive"))
      (node (ref "SV2") (pin "1") (pinfunction "1_1") (pintype "passive"))
      (node (ref "SV4") (pin "1") (pinfunction "1_1") (pintype "passive"))
      (node (ref "SV5") (pin "6") (pinfunction "6_6") (pintype "passive"))
      (node (ref "TP1") (pin "TP") (pinfunction "TP_TP") (pintype "input"))
      (node (ref "U1") (pin "2") (pinfunction "GND_2_2") (pintype "power_in"))
      (node (ref "U1") (pin "3") (pinfunction "GND_3_3") (pintype "power_in"))
      (node (ref "U1") (pin "6") (pinfunction "GND_6_6") (pintype "power_in"))
      (node (ref "U1") (pin "7") (pinfunction "GND_7_7") (pintype "power_in"))
      (node (ref "VI_OUT_JUMPER") (pin "3") (pinfunction "3_3") (pintype "passive"))
      (node (ref "VSS-GND") (pin "1") (pinfunction "1_1") (pintype "passive"))
      (node (ref "VSS-GND") (pin "3") (pinfunction "3_3") (pintype "passive"))
      (node (ref "VSS-GND-1") (pin "1") (pinfunction "1_1") (pintype "passive"))
      (node (ref "VSS-GND-1") (pin "2") (pinfunction "2_2") (pintype "passive"))
      (node (ref "X10") (pin "3") (pinfunction "S_3") (pintype "passive"))
      (node (ref "X10") (pin "5") (pinfunction "S_5") (pintype "passive"))
      (node (ref "X3") (pin "1") (pinfunction "S_1") (pintype "passive"))
      (node (ref "X4") (pin "5") (pinfunction "5_5") (pintype "input"))
      (node (ref "X5") (pin "9") (pinfunction "S_9") (pintype "passive"))
      (node (ref "X6") (pin "9") (pinfunction "S_9") (pintype "passive"))
      (node (ref "X7") (pin "9") (pinfunction "S_9") (pintype "passive"))
      (node (ref "X8") (pin "5") (pinfunction "S_5") (pintype "passive"))
      (node (ref "X9") (pin "5") (pinfunction "S_5") (pintype "passive"))
      (node (ref "X9") (pin "8") (pinfunction "S_8") (pintype "passive"))
    )
    (net (code "92") (name "unconnected-(ICSP-Pad6)") (class "Default")
      (node (ref "ICSP") (pin "6") (pinfunction "6_6") (pintype "passive"))
    )
    (net (code "93") (name "unconnected-(J1-Pad01)") (class "Default")
      (node (ref "J1") (pin "01") (pinfunction "01_01") (pintype "passive"))
    )
    (net (code "94") (name "unconnected-(J1-Pad02)") (class "Default")
      (node (ref "J1") (pin "02") (pinfunction "02_02") (pintype "passive"))
    )
    (net (code "95") (name "unconnected-(J1-Pad03)") (class "Default")
      (node (ref "J1") (pin "03") (pinfunction "03_03") (pintype "passive"))
    )
    (net (code "96") (name "unconnected-(J1-Pad04)") (class "Default")
      (node (ref "J1") (pin "04") (pinfunction "04_04") (pintype "passive"))
    )
    (net (code "97") (name "unconnected-(J1-Pad05)") (class "Default")
      (node (ref "J1") (pin "05") (pinfunction "05_05") (pintype "passive"))
    )
    (net (code "98") (name "unconnected-(J1-Pad06)") (class "Default")
      (node (ref "J1") (pin "06") (pinfunction "06_06") (pintype "passive"))
    )
    (net (code "99") (name "unconnected-(J1-Pad07)") (class "Default")
      (node (ref "J1") (pin "07") (pinfunction "07_07") (pintype "passive"))
    )
    (net (code "100") (name "unconnected-(J1-Pad08)") (class "Default")
      (node (ref "J1") (pin "08") (pinfunction "08_08") (pintype "passive"))
    )
    (net (code "101") (name "unconnected-(J1-Pad09)") (class "Default")
      (node (ref "J1") (pin "09") (pinfunction "09_09") (pintype "passive"))
    )
    (net (code "102") (name "unconnected-(J1-Pad10)") (class "Default")
      (node (ref "J1") (pin "10") (pinfunction "10_10") (pintype "passive"))
    )
    (net (code "103") (name "unconnected-(K1B-O-Pad2)") (class "Default")
      (node (ref "K1") (pin "2") (pinfunction "O_2") (pintype "passive"))
    )
    (net (code "104") (name "unconnected-(S3-Pad1)") (class "Default")
      (node (ref "S3") (pin "1") (pinfunction "1_1") (pintype "bidirectional"))
    )
    (net (code "105") (name "unconnected-(S3-Pad3)") (class "Default")
      (node (ref "S3") (pin "3") (pinfunction "3_3") (pintype "bidirectional"))
    )
    (net (code "106") (name "unconnected-(S4-Pad1)") (class "Default")
      (node (ref "S4") (pin "1") (pinfunction "1_1") (pintype "bidirectional"))
    )
    (net (code "107") (name "unconnected-(S4-Pad3)") (class "Default")
      (node (ref "S4") (pin "3") (pinfunction "3_3") (pintype "bidirectional"))
    )
    (net (code "108") (name "unconnected-(X9F-S-Pad14)") (class "Default")
      (node (ref "X9") (pin "14") (pinfunction "S_14") (pintype "passive"))
    )
    (net (code "109") (name "unconnected-(X9G-S-Pad15)") (class "Default")
      (node (ref "X9") (pin "15") (pinfunction "S_15") (pintype "passive"))
    )
    (net (code "110") (name "unconnected-(X9H-S-Pad16)") (class "Default")
      (node (ref "X9") (pin "16") (pinfunction "S_16") (pintype "passive"))
    )
    (net (code "111") (name "unconnected-(X10A-S-Pad1)") (class "Default")
      (node (ref "X10") (pin "1") (pinfunction "S_1") (pintype "passive"))
    )
    (net (code "112") (name "unconnected-(X10G-S-Pad7)") (class "Default")
      (node (ref "X10") (pin "7") (pinfunction "S_7") (pintype "passive"))
    )
    (net (code "113") (name "unconnected-(X10H-S-Pad8)") (class "Default")
      (node (ref "X10") (pin "8") (pinfunction "S_8") (pintype "passive"))
    )
  )
)
